# TRAFFIC_LIGHT.net
KiCad netlist of a schematic drawn in EAGLE
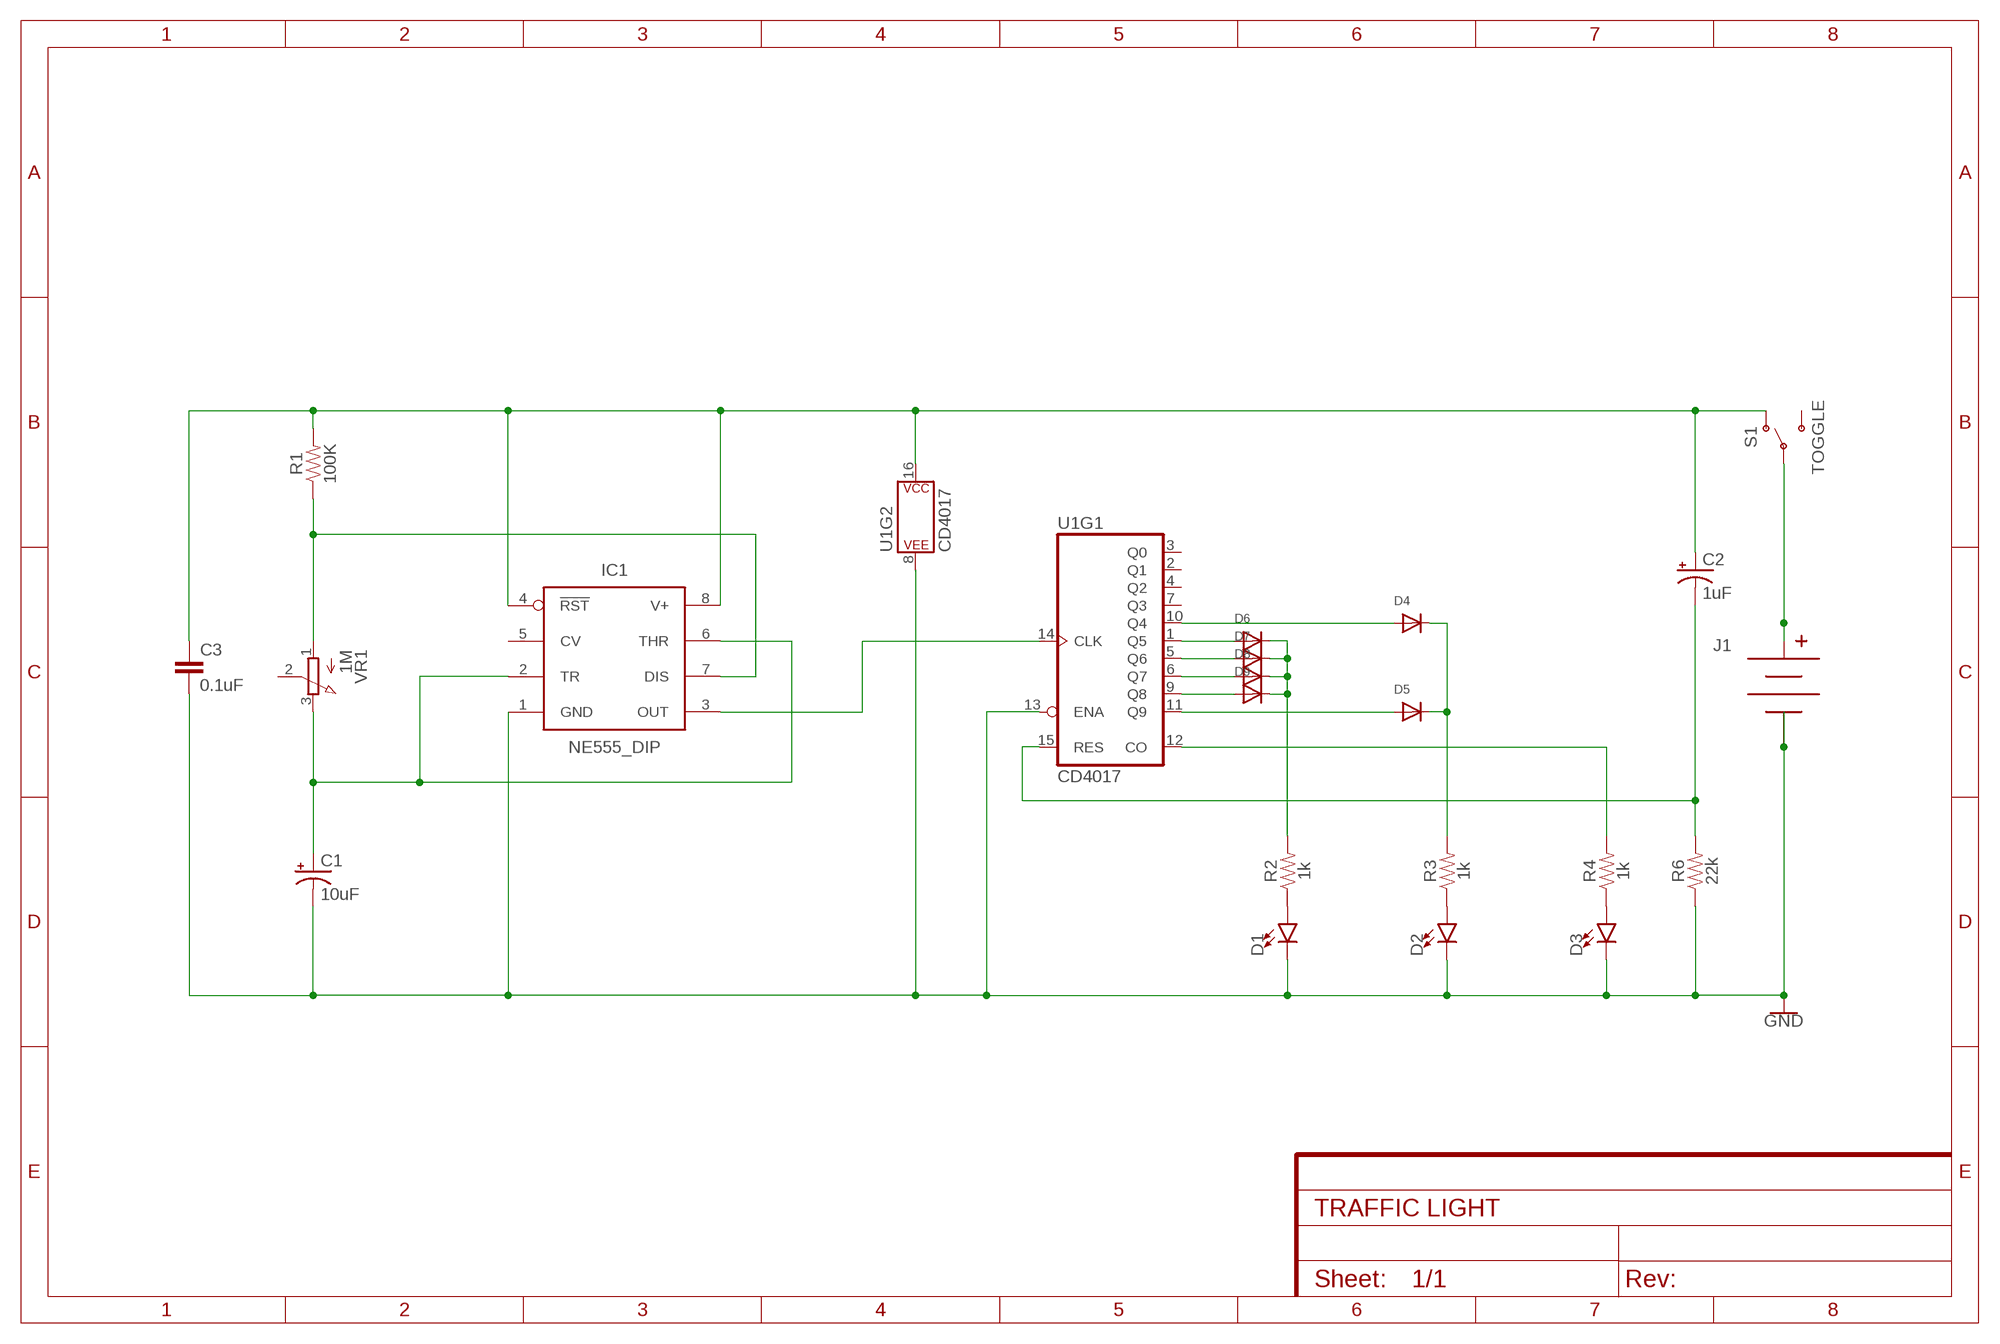
[diagram p0: schematic, sheet 1]

(export (version "E")
  (design (tool "Eeschema 10.0.6"))
  (components
    (comp (ref "C1")
      (value "10uF")
      (footprint "eagle-import:E5-5")
      (libsource (lib "eagle-import") (part "CPOL-USE5-5"))
    )
    (comp (ref "C2")
      (value "1uF")
      (footprint "eagle-import:E5-5")
      (libsource (lib "eagle-import") (part "CPOL-USE5-5"))
    )
    (comp (ref "C3")
      (value "0.1uF")
      (footprint "eagle-import:CAP-PTH-SMALL-KIT")
      (libsource (lib "eagle-import") (part "0.1UF-KIT-EZ-50V-20%"))
    )
    (comp (ref "D1")
      (value "LED5MM")
      (footprint "eagle-import:LED_5MM")
      (libsource (lib "eagle-import") (part "LED5MM"))
    )
    (comp (ref "D2")
      (value "LED5MM")
      (footprint "eagle-import:LED_5MM")
      (libsource (lib "eagle-import") (part "LED5MM"))
    )
    (comp (ref "D3")
      (value "LED5MM")
      (footprint "eagle-import:LED_5MM")
      (libsource (lib "eagle-import") (part "LED5MM"))
    )
    (comp (ref "D4")
      (value "DIODEDO-1N4148")
      (footprint "eagle-import:DO-1N4148")
      (libsource (lib "eagle-import") (part "DIODEDO-1N4148"))
    )
    (comp (ref "D5")
      (value "DIODEDO-1N4148")
      (footprint "eagle-import:DO-1N4148")
      (libsource (lib "eagle-import") (part "DIODEDO-1N4148"))
    )
    (comp (ref "D6")
      (value "DIODEDO-1N4148")
      (footprint "eagle-import:DO-1N4148")
      (libsource (lib "eagle-import") (part "DIODEDO-1N4148"))
    )
    (comp (ref "D7")
      (value "DIODEDO-1N4148")
      (footprint "eagle-import:DO-1N4148")
      (libsource (lib "eagle-import") (part "DIODEDO-1N4148"))
    )
    (comp (ref "D8")
      (value "DIODEDO-1N4148")
      (footprint "eagle-import:DO-1N4148")
      (libsource (lib "eagle-import") (part "DIODEDO-1N4148"))
    )
    (comp (ref "D9")
      (value "DIODEDO-1N4148")
      (footprint "eagle-import:DO-1N4148")
      (libsource (lib "eagle-import") (part "DIODEDO-1N4148"))
    )
    (comp (ref "IC1")
      (value "NE555_DIP")
      (footprint "eagle-import:DIP826W53P254L959H508Q8B")
      (fields (field (name "MANUFACTURER") "Texas Instruments ") (field (name "MPN") "NE555P "))
      (libsource (lib "eagle-import") (part "555_DIPNE"))
    )
    (comp (ref "J1")
      (value "BC9VPC")
      (footprint "eagle-import:BC9VPC")
      (libsource (lib "eagle-import") (part "BC9VPC"))
    )
    (comp (ref "R1")
      (value "100K")
      (footprint "eagle-import:AXIAL-0.3")
      (libsource (lib "eagle-import") (part "1KOHM-HORIZ-1/4W-1%"))
    )
    (comp (ref "R2")
      (value "1k")
      (footprint "eagle-import:AXIAL-0.3")
      (libsource (lib "eagle-import") (part "1KOHM-HORIZ-1/4W-1%"))
    )
    (comp (ref "R3")
      (value "1k")
      (footprint "eagle-import:AXIAL-0.3")
      (libsource (lib "eagle-import") (part "1KOHM-HORIZ-1/4W-1%"))
    )
    (comp (ref "R4")
      (value "1k")
      (footprint "eagle-import:AXIAL-0.3")
      (libsource (lib "eagle-import") (part "1KOHM-HORIZ-1/4W-1%"))
    )
    (comp (ref "R6")
      (value "22k")
      (footprint "eagle-import:AXIAL-0.3")
      (libsource (lib "eagle-import") (part "1KOHM-HORIZ-1/4W-1%"))
    )
    (comp (ref "S1")
      (value "TOGGLE")
      (footprint "eagle-import:SWITCH-SPDT-PTH-8.5X3.7MM")
      (libsource (lib "eagle-import") (part "TOGGLE"))
    )
    (comp (ref "U1")
      (value "CD4017")
      (footprint "eagle-import:DIP16")
      (libsource (lib "eagle-import") (part "CD4017"))
    )
    (comp (ref "VR1")
      (value "1M")
      (footprint "eagle-import:3RP_1610N")
      (libsource (lib "eagle-import") (part "3RP/1610N"))
    )
  )
  (nets
    (net (code "1") (name "GND") (class "Default")
      (node (ref "C1") (pin "-") (pinfunction "-_-") (pintype "passive"))
      (node (ref "C3") (pin "2") (pinfunction "2_2") (pintype "passive"))
      (node (ref "D1") (pin "K") (pinfunction "C_K") (pintype "passive"))
      (node (ref "D2") (pin "K") (pinfunction "C_K") (pintype "passive"))
      (node (ref "D3") (pin "K") (pinfunction "C_K") (pintype "passive"))
      (node (ref "IC1") (pin "1") (pinfunction "GND_1") (pintype "power_in"))
      (node (ref "J1") (pin "V-") (pinfunction "V-_V-") (pintype "bidirectional"))
      (node (ref "R6") (pin "P$1") (pinfunction "1_P$1") (pintype "passive"))
      (node (ref "U1") (pin "13") (pinfunction "ENA_13") (pintype "input"))
      (node (ref "U1") (pin "8") (pinfunction "P$V-_8") (pintype "bidirectional"))
    )
    (net (code "2") (name "Net-(IC1-DIS)") (class "Default")
      (node (ref "IC1") (pin "7") (pinfunction "DIS_7") (pintype "input"))
      (node (ref "R1") (pin "P$1") (pinfunction "1_P$1") (pintype "passive"))
      (node (ref "VR1") (pin "1") (pinfunction "A_1") (pintype "passive"))
    )
    (net (code "3") (name "Net-(IC1-OUT)") (class "Default")
      (node (ref "IC1") (pin "3") (pinfunction "OUT_3") (pintype "output"))
      (node (ref "U1") (pin "14") (pinfunction "CLK_14") (pintype "input"))
    )
    (net (code "4") (name "Net-(IC1-THR)") (class "Default")
      (node (ref "C1") (pin "+") (pinfunction "+_+") (pintype "passive"))
      (node (ref "IC1") (pin "2") (pinfunction "TR_2") (pintype "input"))
      (node (ref "IC1") (pin "6") (pinfunction "THR_6") (pintype "input"))
      (node (ref "VR1") (pin "3") (pinfunction "E_3") (pintype "passive"))
    )
    (net (code "5") (name "Net-(IC1-V+)") (class "Default")
      (node (ref "C2") (pin "+") (pinfunction "+_+") (pintype "passive"))
      (node (ref "C3") (pin "1") (pinfunction "1_1") (pintype "passive"))
      (node (ref "IC1") (pin "4") (pinfunction "~{RST}_4") (pintype "input"))
      (node (ref "IC1") (pin "8") (pinfunction "V+_8") (pintype "power_in"))
      (node (ref "R1") (pin "P$2") (pinfunction "2_P$2") (pintype "passive"))
      (node (ref "S1") (pin "1") (pinfunction "O_1") (pintype "passive"))
      (node (ref "U1") (pin "16") (pinfunction "P$V+_16") (pintype "bidirectional"))
    )
    (net (code "6") (name "Net-(R2-1)") (class "Default")
      (node (ref "D1") (pin "A") (pinfunction "A_A") (pintype "passive"))
      (node (ref "R2") (pin "P$1") (pinfunction "1_P$1") (pintype "passive"))
    )
    (net (code "7") (name "Net-(R2-2)") (class "Default")
      (node (ref "D6") (pin "C") (pinfunction "C_C") (pintype "passive"))
      (node (ref "D7") (pin "C") (pinfunction "C_C") (pintype "passive"))
      (node (ref "D8") (pin "C") (pinfunction "C_C") (pintype "passive"))
      (node (ref "D9") (pin "C") (pinfunction "C_C") (pintype "passive"))
      (node (ref "R2") (pin "P$2") (pinfunction "2_P$2") (pintype "passive"))
    )
    (net (code "8") (name "Net-(R3-1)") (class "Default")
      (node (ref "D2") (pin "A") (pinfunction "A_A") (pintype "passive"))
      (node (ref "R3") (pin "P$1") (pinfunction "1_P$1") (pintype "passive"))
    )
    (net (code "9") (name "Net-(R3-2)") (class "Default")
      (node (ref "D4") (pin "C") (pinfunction "C_C") (pintype "passive"))
      (node (ref "D5") (pin "C") (pinfunction "C_C") (pintype "passive"))
      (node (ref "R3") (pin "P$2") (pinfunction "2_P$2") (pintype "passive"))
    )
    (net (code "10") (name "Net-(R4-1)") (class "Default")
      (node (ref "D3") (pin "A") (pinfunction "A_A") (pintype "passive"))
      (node (ref "R4") (pin "P$1") (pinfunction "1_P$1") (pintype "passive"))
    )
    (net (code "11") (name "Net-(R4-2)") (class "Default")
      (node (ref "R4") (pin "P$2") (pinfunction "2_P$2") (pintype "passive"))
      (node (ref "U1") (pin "12") (pinfunction "CO_12") (pintype "output"))
    )
    (net (code "12") (name "Net-(R6-2)") (class "Default")
      (node (ref "C2") (pin "-") (pinfunction "-_-") (pintype "passive"))
      (node (ref "R6") (pin "P$2") (pinfunction "2_P$2") (pintype "passive"))
      (node (ref "U1") (pin "15") (pinfunction "RES_15") (pintype "input"))
    )
    (net (code "13") (name "Net-(S1-P)") (class "Default")
      (node (ref "J1") (pin "V+") (pinfunction "V+_V+") (pintype "bidirectional"))
      (node (ref "S1") (pin "2") (pinfunction "P_2") (pintype "passive"))
    )
    (net (code "14") (name "Net-(U1A-Q4)") (class "Default")
      (node (ref "D4") (pin "A") (pinfunction "A_A") (pintype "passive"))
      (node (ref "U1") (pin "10") (pinfunction "Q4_10") (pintype "output"))
    )
    (net (code "15") (name "Net-(U1A-Q5)") (class "Default")
      (node (ref "D6") (pin "A") (pinfunction "A_A") (pintype "passive"))
      (node (ref "U1") (pin "1") (pinfunction "Q5_1") (pintype "output"))
    )
    (net (code "16") (name "Net-(U1A-Q6)") (class "Default")
      (node (ref "D7") (pin "A") (pinfunction "A_A") (pintype "passive"))
      (node (ref "U1") (pin "5") (pinfunction "Q6_5") (pintype "output"))
    )
    (net (code "17") (name "Net-(U1A-Q7)") (class "Default")
      (node (ref "D8") (pin "A") (pinfunction "A_A") (pintype "passive"))
      (node (ref "U1") (pin "6") (pinfunction "Q7_6") (pintype "output"))
    )
    (net (code "18") (name "Net-(U1A-Q8)") (class "Default")
      (node (ref "D9") (pin "A") (pinfunction "A_A") (pintype "passive"))
      (node (ref "U1") (pin "9") (pinfunction "Q8_9") (pintype "output"))
    )
    (net (code "19") (name "Net-(U1A-Q9)") (class "Default")
      (node (ref "D5") (pin "A") (pinfunction "A_A") (pintype "passive"))
      (node (ref "U1") (pin "11") (pinfunction "Q9_11") (pintype "output"))
    )
    (net (code "20") (name "unconnected-(IC1-CV-Pad5)") (class "Default")
      (node (ref "IC1") (pin "5") (pinfunction "CV_5") (pintype "input"))
    )
    (net (code "21") (name "unconnected-(S1-S-Pad3)") (class "Default")
      (node (ref "S1") (pin "3") (pinfunction "S_3") (pintype "passive"))
    )
    (net (code "22") (name "unconnected-(U1A-Q0-Pad3)") (class "Default")
      (node (ref "U1") (pin "3") (pinfunction "Q0_3") (pintype "output"))
    )
    (net (code "23") (name "unconnected-(U1A-Q1-Pad2)") (class "Default")
      (node (ref "U1") (pin "2") (pinfunction "Q1_2") (pintype "output"))
    )
    (net (code "24") (name "unconnected-(U1A-Q2-Pad4)") (class "Default")
      (node (ref "U1") (pin "4") (pinfunction "Q2_4") (pintype "output"))
    )
    (net (code "25") (name "unconnected-(U1A-Q3-Pad7)") (class "Default")
      (node (ref "U1") (pin "7") (pinfunction "Q3_7") (pintype "output"))
    )
    (net (code "26") (name "unconnected-(VR1-S-Pad2)") (class "Default")
      (node (ref "VR1") (pin "2") (pinfunction "S_2") (pintype "passive"))
    )
  )
)
